# ESP.net
KiCad netlist of a schematic drawn in Altium Designer
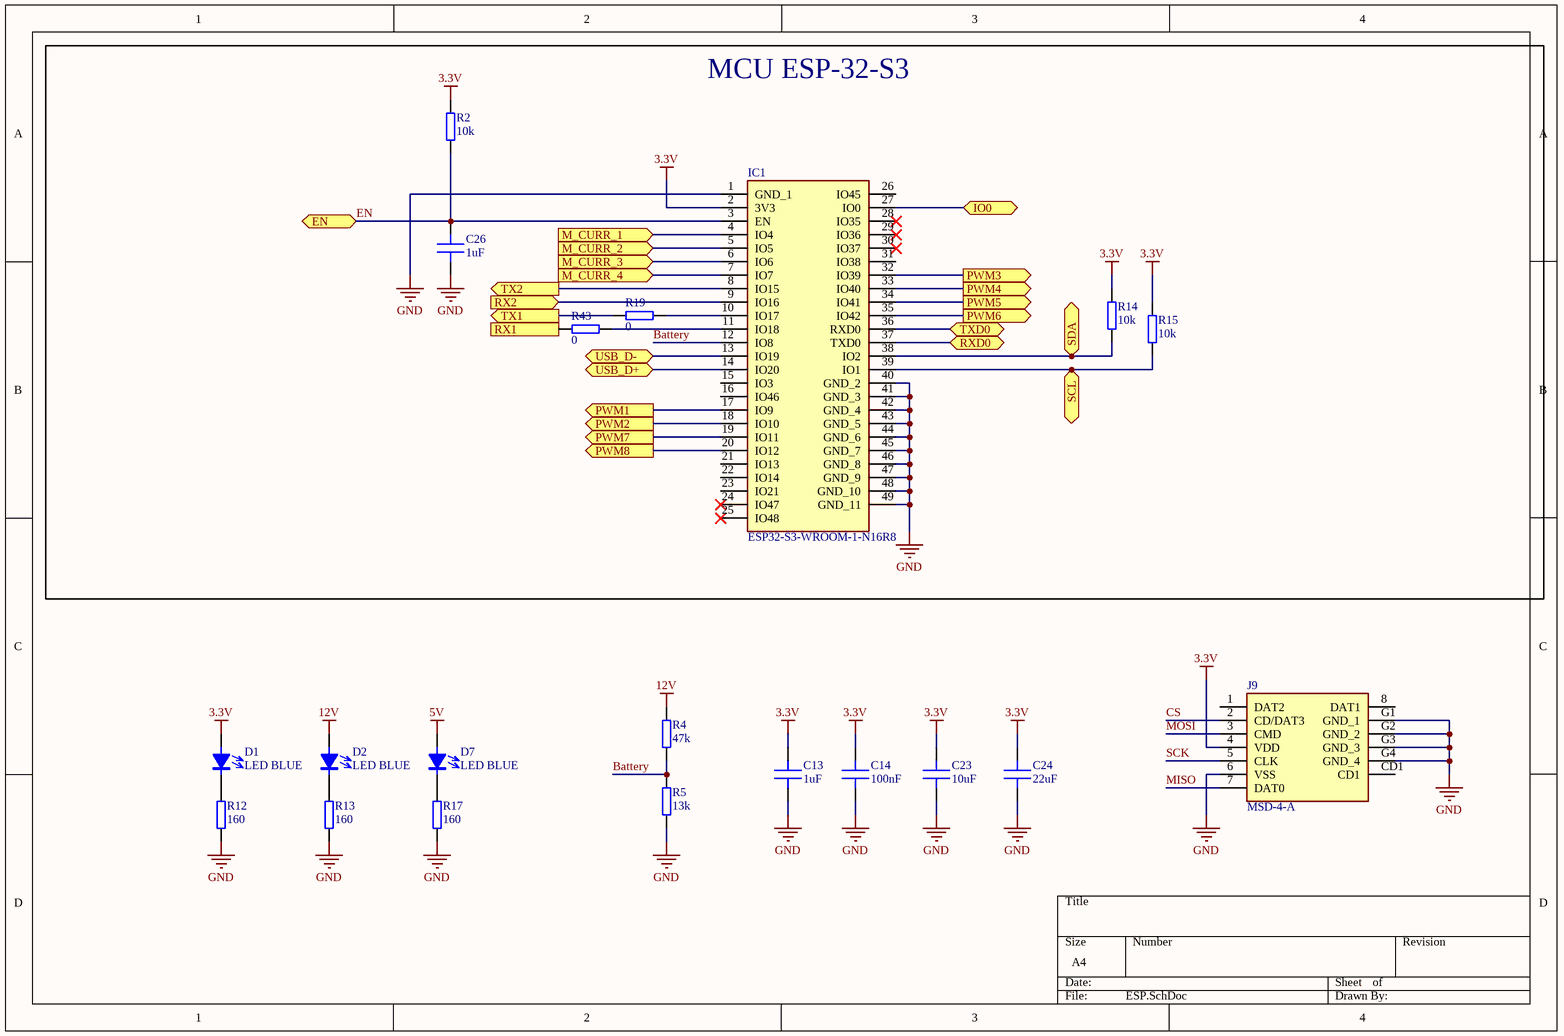
[diagram p0: ESP.SchDoc]

(export (version "E")
  (design (tool "Eeschema 10.0.6"))
  (components
    (comp (ref "C13")
      (value "1uF")
      (footprint "C 0402")
      (description "MLCC Capacitor")
      (libsource (lib "Components") (part "Capacitor"))
    )
    (comp (ref "C14")
      (value "100nF")
      (footprint "C 0402")
      (description "MLCC Capacitor")
      (libsource (lib "Components") (part "Capacitor"))
    )
    (comp (ref "C23")
      (value "10uF")
      (footprint "C 0402")
      (description "MLCC Capacitor")
      (libsource (lib "Components") (part "Capacitor"))
    )
    (comp (ref "C24")
      (value "22uF")
      (footprint "C 0402")
      (description "MLCC Capacitor")
      (libsource (lib "Components") (part "Capacitor"))
    )
    (comp (ref "C26")
      (value "1uF")
      (footprint "C 0402")
      (description "MLCC Capacitor")
      (libsource (lib "Components") (part "Capacitor"))
    )
    (comp (ref "D1")
      (value "LED BLUE")
      (footprint "LED 0603 BLUE")
      (libsource (lib "Components") (part "LED BLUE"))
    )
    (comp (ref "D2")
      (value "LED BLUE")
      (footprint "LED 0603 BLUE")
      (libsource (lib "Components") (part "LED BLUE"))
    )
    (comp (ref "D7")
      (value "LED BLUE")
      (footprint "LED 0603 BLUE")
      (libsource (lib "Components") (part "LED BLUE"))
    )
    (comp (ref "IC1")
      (value "ESP32-S3-WROOM-1-N16R8")
      (footprint "lf_esp_pcb_lib:ESP32S3WROOM1N16R8")
      (description "Integrated Circuit")
      (fields (field (name "MOUSER PART NUMBER") "356-ESP32S3WRM1N16R8"))
      (libsource (lib "lf_esp_sch_lib") (part "ESP32-S3-WROOM-1-N16R8"))
    )
    (comp (ref "J9")
      (value "MSD-4-A")
      (footprint "SamacSys:MSD4A")
      (description "Connector")
      (fields (field (name "MOUSER PART NUMBER") "179-MSD-4-A"))
      (libsource (lib "*") (part "MSD-4-A"))
    )
    (comp (ref "R2")
      (value "10k")
      (footprint "R 0402")
      (description "General pourpouse resistor")
      (libsource (lib "Components") (part "Resistor"))
    )
    (comp (ref "R4")
      (value "47k")
      (footprint "R 0402")
      (description "General pourpouse resistor")
      (libsource (lib "Components") (part "Resistor"))
    )
    (comp (ref "R5")
      (value "13k")
      (footprint "R 0402")
      (description "General pourpouse resistor")
      (libsource (lib "Components") (part "Resistor"))
    )
    (comp (ref "R12")
      (value "160")
      (footprint "R 0402")
      (description "General pourpouse resistor")
      (libsource (lib "Components") (part "Resistor"))
    )
    (comp (ref "R13")
      (value "160")
      (footprint "R 0402")
      (description "General pourpouse resistor")
      (libsource (lib "Components") (part "Resistor"))
    )
    (comp (ref "R14")
      (value "10k")
      (footprint "R 0402")
      (description "General pourpouse resistor")
      (libsource (lib "Components") (part "Resistor"))
    )
    (comp (ref "R15")
      (value "10k")
      (footprint "R 0402")
      (description "General pourpouse resistor")
      (libsource (lib "Components") (part "Resistor"))
    )
    (comp (ref "R17")
      (value "160")
      (footprint "R 0402")
      (description "General pourpouse resistor")
      (libsource (lib "Components") (part "Resistor"))
    )
    (comp (ref "R19")
      (value "0")
      (footprint "R 0402")
      (description "General pourpouse resistor")
      (libsource (lib "Components") (part "Resistor"))
    )
    (comp (ref "R43")
      (value "0")
      (footprint "R 0402")
      (description "General pourpouse resistor")
      (libsource (lib "Components") (part "Resistor"))
    )
  )
  (nets
    (net (code "1") (name "/Battery") (class "Default")
      (node (ref "IC1") (pin "12") (pinfunction "IO8_12") (pintype "passive"))
      (node (ref "R4") (pin "1") (pinfunction "1_1") (pintype "passive"))
      (node (ref "R5") (pin "2") (pinfunction "2_2") (pintype "passive"))
    )
    (net (code "2") (name "/CS") (class "Default")
      (node (ref "J9") (pin "2") (pinfunction "CD/DAT3_2") (pintype "passive"))
    )
    (net (code "3") (name "/EN") (class "Default")
      (node (ref "C26") (pin "1") (pinfunction "1_1") (pintype "passive"))
      (node (ref "IC1") (pin "3") (pinfunction "EN_3") (pintype "passive"))
      (node (ref "R2") (pin "1") (pinfunction "1_1") (pintype "passive"))
    )
    (net (code "4") (name "/IO0") (class "Default")
      (node (ref "IC1") (pin "27") (pinfunction "IO0_27") (pintype "passive"))
    )
    (net (code "5") (name "/MISO") (class "Default")
      (node (ref "J9") (pin "7") (pinfunction "DAT0_7") (pintype "passive"))
    )
    (net (code "6") (name "/MOSI") (class "Default")
      (node (ref "J9") (pin "3") (pinfunction "CMD_3") (pintype "passive"))
    )
    (net (code "7") (name "/M_CURR_1") (class "Default")
      (node (ref "IC1") (pin "4") (pinfunction "IO4_4") (pintype "passive"))
    )
    (net (code "8") (name "/M_CURR_2") (class "Default")
      (node (ref "IC1") (pin "5") (pinfunction "IO5_5") (pintype "passive"))
    )
    (net (code "9") (name "/M_CURR_3") (class "Default")
      (node (ref "IC1") (pin "6") (pinfunction "IO6_6") (pintype "passive"))
    )
    (net (code "10") (name "/M_CURR_4") (class "Default")
      (node (ref "IC1") (pin "7") (pinfunction "IO7_7") (pintype "passive"))
    )
    (net (code "11") (name "/PWM1") (class "Default")
      (node (ref "IC1") (pin "17") (pinfunction "IO9_17") (pintype "passive"))
    )
    (net (code "12") (name "/PWM2") (class "Default")
      (node (ref "IC1") (pin "18") (pinfunction "IO10_18") (pintype "passive"))
    )
    (net (code "13") (name "/PWM3") (class "Default")
      (node (ref "IC1") (pin "32") (pinfunction "IO39_32") (pintype "passive"))
    )
    (net (code "14") (name "/PWM4") (class "Default")
      (node (ref "IC1") (pin "33") (pinfunction "IO40_33") (pintype "passive"))
    )
    (net (code "15") (name "/PWM5") (class "Default")
      (node (ref "IC1") (pin "34") (pinfunction "IO41_34") (pintype "passive"))
    )
    (net (code "16") (name "/PWM6") (class "Default")
      (node (ref "IC1") (pin "35") (pinfunction "IO42_35") (pintype "passive"))
    )
    (net (code "17") (name "/PWM7") (class "Default")
      (node (ref "IC1") (pin "19") (pinfunction "IO11_19") (pintype "passive"))
    )
    (net (code "18") (name "/PWM8") (class "Default")
      (node (ref "IC1") (pin "20") (pinfunction "IO12_20") (pintype "passive"))
    )
    (net (code "19") (name "/RX1") (class "Default")
      (node (ref "R43") (pin "2") (pinfunction "2_2") (pintype "passive"))
    )
    (net (code "20") (name "/RX2") (class "Default")
      (node (ref "IC1") (pin "9") (pinfunction "IO16_9") (pintype "passive"))
    )
    (net (code "21") (name "/RXD0") (class "Default")
      (node (ref "IC1") (pin "37") (pinfunction "TXD0_37") (pintype "passive"))
    )
    (net (code "22") (name "/SCK") (class "Default")
      (node (ref "J9") (pin "5") (pinfunction "CLK_5") (pintype "passive"))
    )
    (net (code "23") (name "/SCL") (class "Default")
      (node (ref "IC1") (pin "39") (pinfunction "IO1_39") (pintype "passive"))
      (node (ref "R15") (pin "1") (pinfunction "1_1") (pintype "passive"))
    )
    (net (code "24") (name "/SDA") (class "Default")
      (node (ref "IC1") (pin "38") (pinfunction "IO2_38") (pintype "passive"))
      (node (ref "R14") (pin "1") (pinfunction "1_1") (pintype "passive"))
    )
    (net (code "25") (name "/TX1") (class "Default")
      (node (ref "R19") (pin "2") (pinfunction "2_2") (pintype "passive"))
    )
    (net (code "26") (name "/TX2") (class "Default")
      (node (ref "IC1") (pin "8") (pinfunction "IO15_8") (pintype "passive"))
    )
    (net (code "27") (name "/TXD0") (class "Default")
      (node (ref "IC1") (pin "36") (pinfunction "RXD0_36") (pintype "passive"))
    )
    (net (code "28") (name "/USB_D+") (class "Default")
      (node (ref "IC1") (pin "14") (pinfunction "IO20_14") (pintype "passive"))
    )
    (net (code "29") (name "/USB_D-") (class "Default")
      (node (ref "IC1") (pin "13") (pinfunction "IO19_13") (pintype "passive"))
    )
    (net (code "30") (name "3.3V") (class "Default")
      (node (ref "C13") (pin "1") (pinfunction "1_1") (pintype "passive"))
      (node (ref "C14") (pin "1") (pinfunction "1_1") (pintype "passive"))
      (node (ref "C23") (pin "1") (pinfunction "1_1") (pintype "passive"))
      (node (ref "C24") (pin "1") (pinfunction "1_1") (pintype "passive"))
      (node (ref "D1") (pin "1") (pinfunction "1_1") (pintype "passive"))
      (node (ref "IC1") (pin "2") (pinfunction "3V3_2") (pintype "passive"))
      (node (ref "J9") (pin "4") (pinfunction "VDD_4") (pintype "passive"))
      (node (ref "R14") (pin "2") (pinfunction "2_2") (pintype "passive"))
      (node (ref "R15") (pin "2") (pinfunction "2_2") (pintype "passive"))
      (node (ref "R2") (pin "2") (pinfunction "2_2") (pintype "passive"))
    )
    (net (code "31") (name "5V") (class "Default")
      (node (ref "D7") (pin "1") (pinfunction "1_1") (pintype "passive"))
    )
    (net (code "32") (name "12V") (class "Default")
      (node (ref "D2") (pin "1") (pinfunction "1_1") (pintype "passive"))
      (node (ref "R4") (pin "2") (pinfunction "2_2") (pintype "passive"))
    )
    (net (code "33") (name "GND") (class "Default")
      (node (ref "C13") (pin "2") (pinfunction "2_2") (pintype "passive"))
      (node (ref "C14") (pin "2") (pinfunction "2_2") (pintype "passive"))
      (node (ref "C23") (pin "2") (pinfunction "2_2") (pintype "passive"))
      (node (ref "C24") (pin "2") (pinfunction "2_2") (pintype "passive"))
      (node (ref "C26") (pin "2") (pinfunction "2_2") (pintype "passive"))
      (node (ref "IC1") (pin "1") (pinfunction "GND_1_1") (pintype "passive"))
      (node (ref "IC1") (pin "40") (pinfunction "GND_2_40") (pintype "passive"))
      (node (ref "IC1") (pin "41") (pinfunction "GND_3_41") (pintype "passive"))
      (node (ref "IC1") (pin "42") (pinfunction "GND_4_42") (pintype "passive"))
      (node (ref "IC1") (pin "43") (pinfunction "GND_5_43") (pintype "passive"))
      (node (ref "IC1") (pin "44") (pinfunction "GND_6_44") (pintype "passive"))
      (node (ref "IC1") (pin "45") (pinfunction "GND_7_45") (pintype "passive"))
      (node (ref "IC1") (pin "46") (pinfunction "GND_8_46") (pintype "passive"))
      (node (ref "IC1") (pin "47") (pinfunction "GND_9_47") (pintype "passive"))
      (node (ref "IC1") (pin "48") (pinfunction "GND_10_48") (pintype "passive"))
      (node (ref "IC1") (pin "49") (pinfunction "GND_11_49") (pintype "passive"))
      (node (ref "J9") (pin "6") (pinfunction "VSS_6") (pintype "passive"))
      (node (ref "J9") (pin "G1") (pinfunction "GND_1_G1") (pintype "passive"))
      (node (ref "J9") (pin "G2") (pinfunction "GND_2_G2") (pintype "passive"))
      (node (ref "J9") (pin "G3") (pinfunction "GND_3_G3") (pintype "passive"))
      (node (ref "J9") (pin "G4") (pinfunction "GND_4_G4") (pintype "passive"))
      (node (ref "R12") (pin "1") (pinfunction "1_1") (pintype "passive"))
      (node (ref "R13") (pin "1") (pinfunction "1_1") (pintype "passive"))
      (node (ref "R17") (pin "1") (pinfunction "1_1") (pintype "passive"))
      (node (ref "R5") (pin "1") (pinfunction "1_1") (pintype "passive"))
    )
    (net (code "34") (name "Net-(D1-Pad2)") (class "Default")
      (node (ref "D1") (pin "2") (pinfunction "2_2") (pintype "passive"))
      (node (ref "R12") (pin "2") (pinfunction "2_2") (pintype "passive"))
    )
    (net (code "35") (name "Net-(D2-Pad2)") (class "Default")
      (node (ref "D2") (pin "2") (pinfunction "2_2") (pintype "passive"))
      (node (ref "R13") (pin "2") (pinfunction "2_2") (pintype "passive"))
    )
    (net (code "36") (name "Net-(D7-Pad2)") (class "Default")
      (node (ref "D7") (pin "2") (pinfunction "2_2") (pintype "passive"))
      (node (ref "R17") (pin "2") (pinfunction "2_2") (pintype "passive"))
    )
    (net (code "37") (name "Net-(IC1-IO17)") (class "Default")
      (node (ref "IC1") (pin "10") (pinfunction "IO17_10") (pintype "passive"))
      (node (ref "R19") (pin "1") (pinfunction "1_1") (pintype "passive"))
    )
    (net (code "38") (name "Net-(IC1-IO18)") (class "Default")
      (node (ref "IC1") (pin "11") (pinfunction "IO18_11") (pintype "passive"))
      (node (ref "R43") (pin "1") (pinfunction "1_1") (pintype "passive"))
    )
    (net (code "39") (name "unconnected-(IC1-IO3-Pad15)") (class "Default")
      (node (ref "IC1") (pin "15") (pinfunction "IO3_15") (pintype "passive"))
    )
    (net (code "40") (name "unconnected-(IC1-IO13-Pad21)") (class "Default")
      (node (ref "IC1") (pin "21") (pinfunction "IO13_21") (pintype "passive"))
    )
    (net (code "41") (name "unconnected-(IC1-IO14-Pad22)") (class "Default")
      (node (ref "IC1") (pin "22") (pinfunction "IO14_22") (pintype "passive"))
    )
    (net (code "42") (name "unconnected-(IC1-IO21-Pad23)") (class "Default")
      (node (ref "IC1") (pin "23") (pinfunction "IO21_23") (pintype "passive"))
    )
    (net (code "43") (name "unconnected-(IC1-IO35-Pad28)") (class "Default")
      (node (ref "IC1") (pin "28") (pinfunction "IO35_28") (pintype "passive+no_connect"))
    )
    (net (code "44") (name "unconnected-(IC1-IO36-Pad29)") (class "Default")
      (node (ref "IC1") (pin "29") (pinfunction "IO36_29") (pintype "passive+no_connect"))
    )
    (net (code "45") (name "unconnected-(IC1-IO37-Pad30)") (class "Default")
      (node (ref "IC1") (pin "30") (pinfunction "IO37_30") (pintype "passive+no_connect"))
    )
    (net (code "46") (name "unconnected-(IC1-IO38-Pad31)") (class "Default")
      (node (ref "IC1") (pin "31") (pinfunction "IO38_31") (pintype "passive"))
    )
    (net (code "47") (name "unconnected-(IC1-IO45-Pad26)") (class "Default")
      (node (ref "IC1") (pin "26") (pinfunction "IO45_26") (pintype "passive"))
    )
    (net (code "48") (name "unconnected-(IC1-IO46-Pad16)") (class "Default")
      (node (ref "IC1") (pin "16") (pinfunction "IO46_16") (pintype "passive"))
    )
    (net (code "49") (name "unconnected-(IC1-IO47-Pad24)") (class "Default")
      (node (ref "IC1") (pin "24") (pinfunction "IO47_24") (pintype "passive+no_connect"))
    )
    (net (code "50") (name "unconnected-(IC1-IO48-Pad25)") (class "Default")
      (node (ref "IC1") (pin "25") (pinfunction "IO48_25") (pintype "passive+no_connect"))
    )
    (net (code "51") (name "unconnected-(J9-DAT1-Pad8)") (class "Default")
      (node (ref "J9") (pin "8") (pinfunction "DAT1_8") (pintype "passive"))
    )
    (net (code "52") (name "unconnected-(J9-DAT2-Pad1)") (class "Default")
      (node (ref "J9") (pin "1") (pinfunction "DAT2_1") (pintype "passive"))
    )
    (net (code "53") (name "unconnected-(J9-PadCD1)") (class "Default")
      (node (ref "J9") (pin "CD1") (pinfunction "CD1_CD1") (pintype "passive"))
    )
  )
)
